# IrrigationManager.net
KiCad netlist of a schematic drawn in EAGLE
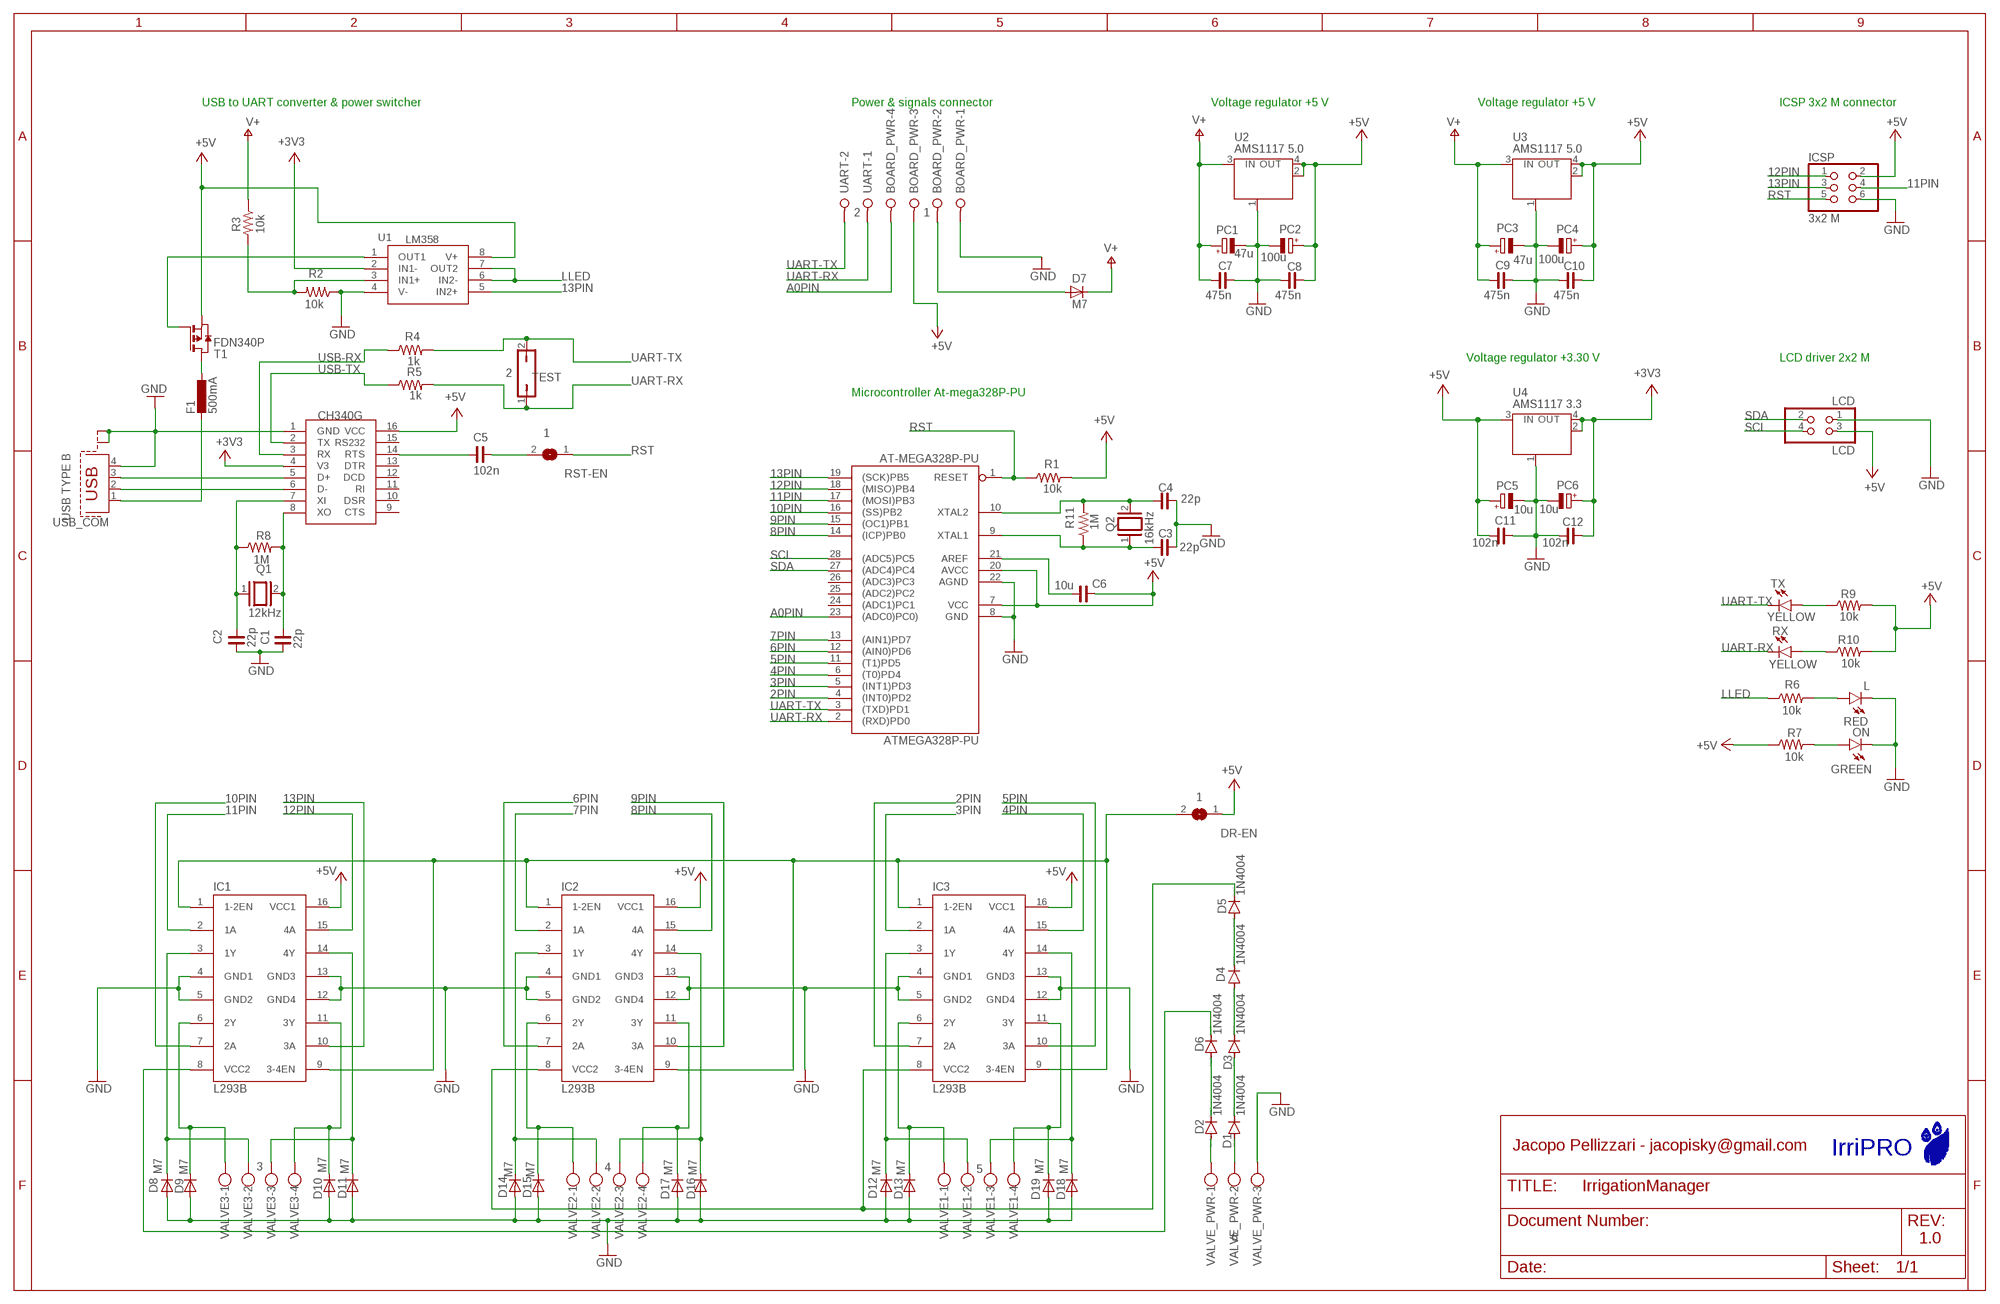
[diagram p0: schematic, sheet 1]

(export (version "E")
  (design (tool "Eeschema 10.0.6"))
  (components
    (comp (ref "AT-MEGA328P-PU")
      (value "ATMEGA328P-PU")
      (footprint "eagle-import:DIL28-3")
      (libsource (lib "eagle-import") (part "ATMEGA328P-PU"))
    )
    (comp (ref "BOARD_PWR")
      (value "1")
      (footprint "eagle-import:W237-4P")
      (libsource (lib "eagle-import") (part "con-wago-508_196_W237-04P"))
    )
    (comp (ref "C1")
      (value "22p")
      (footprint "eagle-import:C1206")
      (libsource (lib "eagle-import") (part "C_1206"))
    )
    (comp (ref "C2")
      (value "22p")
      (footprint "eagle-import:C1206")
      (libsource (lib "eagle-import") (part "C_1206"))
    )
    (comp (ref "C3")
      (value "22p")
      (footprint "eagle-import:C1206")
      (libsource (lib "eagle-import") (part "C_1206"))
    )
    (comp (ref "C4")
      (value "22p")
      (footprint "eagle-import:C1206")
      (libsource (lib "eagle-import") (part "C_1206"))
    )
    (comp (ref "C5")
      (value "102n")
      (footprint "eagle-import:C1206")
      (libsource (lib "eagle-import") (part "C_1206"))
    )
    (comp (ref "C6")
      (value "10u")
      (footprint "eagle-import:C1206")
      (libsource (lib "eagle-import") (part "C_1206"))
    )
    (comp (ref "C7")
      (value "475n")
      (footprint "eagle-import:C1206")
      (libsource (lib "eagle-import") (part "C_1206"))
    )
    (comp (ref "C8")
      (value "475n")
      (footprint "eagle-import:C1206")
      (libsource (lib "eagle-import") (part "C_1206"))
    )
    (comp (ref "C9")
      (value "475n")
      (footprint "eagle-import:C1206")
      (libsource (lib "eagle-import") (part "C_1206"))
    )
    (comp (ref "C10")
      (value "475n")
      (footprint "eagle-import:C1206")
      (libsource (lib "eagle-import") (part "C_1206"))
    )
    (comp (ref "C11")
      (value "102n")
      (footprint "eagle-import:C1206")
      (libsource (lib "eagle-import") (part "C_1206"))
    )
    (comp (ref "C12")
      (value "102n")
      (footprint "eagle-import:C1206")
      (libsource (lib "eagle-import") (part "C_1206"))
    )
    (comp (ref "D1")
      (value "1N4004")
      (footprint "eagle-import:DO41-10")
      (libsource (lib "eagle-import") (part "1N4004"))
    )
    (comp (ref "D2")
      (value "1N4004")
      (footprint "eagle-import:DO41-10")
      (libsource (lib "eagle-import") (part "1N4004"))
    )
    (comp (ref "D3")
      (value "1N4004")
      (footprint "eagle-import:DO41-10")
      (libsource (lib "eagle-import") (part "1N4004"))
    )
    (comp (ref "D4")
      (value "1N4004")
      (footprint "eagle-import:DO41-10")
      (libsource (lib "eagle-import") (part "1N4004"))
    )
    (comp (ref "D5")
      (value "1N4004")
      (footprint "eagle-import:DO41-10")
      (libsource (lib "eagle-import") (part "1N4004"))
    )
    (comp (ref "D6")
      (value "1N4004")
      (footprint "eagle-import:DO41-10")
      (libsource (lib "eagle-import") (part "1N4004"))
    )
    (comp (ref "D7")
      (value "M7")
      (footprint "eagle-import:SMB")
      (libsource (lib "eagle-import") (part "DIODE-SMB"))
    )
    (comp (ref "D8")
      (value "M7")
      (footprint "eagle-import:SMB")
      (libsource (lib "eagle-import") (part "DIODE-SMB"))
    )
    (comp (ref "D9")
      (value "M7")
      (footprint "eagle-import:SMB")
      (libsource (lib "eagle-import") (part "DIODE-SMB"))
    )
    (comp (ref "D10")
      (value "M7")
      (footprint "eagle-import:SMB")
      (libsource (lib "eagle-import") (part "DIODE-SMB"))
    )
    (comp (ref "D11")
      (value "M7")
      (footprint "eagle-import:SMB")
      (libsource (lib "eagle-import") (part "DIODE-SMB"))
    )
    (comp (ref "D12")
      (value "M7")
      (footprint "eagle-import:SMB")
      (libsource (lib "eagle-import") (part "DIODE-SMB"))
    )
    (comp (ref "D13")
      (value "M7")
      (footprint "eagle-import:SMB")
      (libsource (lib "eagle-import") (part "DIODE-SMB"))
    )
    (comp (ref "D14")
      (value "M7")
      (footprint "eagle-import:SMB")
      (libsource (lib "eagle-import") (part "DIODE-SMB"))
    )
    (comp (ref "D15")
      (value "M7")
      (footprint "eagle-import:SMB")
      (libsource (lib "eagle-import") (part "DIODE-SMB"))
    )
    (comp (ref "D16")
      (value "M7")
      (footprint "eagle-import:SMB")
      (libsource (lib "eagle-import") (part "DIODE-SMB"))
    )
    (comp (ref "D17")
      (value "M7")
      (footprint "eagle-import:SMB")
      (libsource (lib "eagle-import") (part "DIODE-SMB"))
    )
    (comp (ref "D18")
      (value "M7")
      (footprint "eagle-import:SMB")
      (libsource (lib "eagle-import") (part "DIODE-SMB"))
    )
    (comp (ref "D19")
      (value "M7")
      (footprint "eagle-import:SMB")
      (libsource (lib "eagle-import") (part "DIODE-SMB"))
    )
    (comp (ref "DR-EN")
      (value "1")
      (footprint "eagle-import:SJ")
      (libsource (lib "eagle-import") (part "SJ"))
    )
    (comp (ref "F1")
      (value "500mA")
      (footprint "eagle-import:L1812")
      (libsource (lib "eagle-import") (part "L-EUL1812"))
    )
    (comp (ref "IC1")
      (value "L293B")
      (footprint "eagle-import:DIL16")
      (fields (field (name "MPN") "L293D"))
      (libsource (lib "eagle-import") (part "L293D"))
    )
    (comp (ref "IC2")
      (value "L293B")
      (footprint "eagle-import:DIL16")
      (fields (field (name "MPN") "L293D"))
      (libsource (lib "eagle-import") (part "L293D"))
    )
    (comp (ref "IC3")
      (value "L293B")
      (footprint "eagle-import:DIL16")
      (fields (field (name "MPN") "L293D"))
      (libsource (lib "eagle-import") (part "L293D"))
    )
    (comp (ref "ICSP")
      (value "3x2 M")
      (footprint "eagle-import:2X03")
      (libsource (lib "eagle-import") (part "PINHD-2X3"))
    )
    (comp (ref "L")
      (value "RED")
      (footprint "eagle-import:CHIPLED_1206")
      (libsource (lib "eagle-import") (part "LEDCHIPLED_1206"))
    )
    (comp (ref "LCD")
      (value "LCD")
      (footprint "eagle-import:2X02")
      (libsource (lib "eagle-import") (part "PINHD-2X2"))
    )
    (comp (ref "ON")
      (value "GREEN")
      (footprint "eagle-import:CHIPLED_1206")
      (libsource (lib "eagle-import") (part "LEDCHIPLED_1206"))
    )
    (comp (ref "PC1")
      (value "47u")
      (footprint "eagle-import:PANASONIC_D")
      (libsource (lib "eagle-import") (part "CPOL-EUD"))
    )
    (comp (ref "PC2")
      (value "100u")
      (footprint "eagle-import:PANASONIC_D")
      (libsource (lib "eagle-import") (part "CPOL-EUD"))
    )
    (comp (ref "PC3")
      (value "47u")
      (footprint "eagle-import:PANASONIC_D")
      (libsource (lib "eagle-import") (part "CPOL-EUD"))
    )
    (comp (ref "PC4")
      (value "100u")
      (footprint "eagle-import:PANASONIC_D")
      (libsource (lib "eagle-import") (part "CPOL-EUD"))
    )
    (comp (ref "PC5")
      (value "10u")
      (footprint "eagle-import:153CLV-0405")
      (libsource (lib "eagle-import") (part "rcl_334_CPOL-EU153CLV-0405"))
    )
    (comp (ref "PC6")
      (value "10u")
      (footprint "eagle-import:153CLV-0405")
      (libsource (lib "eagle-import") (part "rcl_334_CPOL-EU153CLV-0405"))
    )
    (comp (ref "Q1")
      (value "12kHz")
      (footprint "eagle-import:QS")
      (libsource (lib "eagle-import") (part "XTAL/S"))
    )
    (comp (ref "Q2")
      (value "16kHz")
      (footprint "eagle-import:QS")
      (libsource (lib "eagle-import") (part "XTAL/S"))
    )
    (comp (ref "R1")
      (value "10k")
      (footprint "eagle-import:RES_1206")
      (fields
        (field (name "DIGIKEY_PART_NUMBER") "P0.0ETR-ND")
        (field (name "MANUFACTURER") "Panasonic Electronic Components")
        (field (name "MPN") "ERJ-8GEY0R00V")
        (field (name "CREATED_BY") "PCBLayout.com")
      )
      (libsource (lib "eagle-import") (part "ERJ-8GEY0R00V"))
    )
    (comp (ref "R2")
      (value "10k")
      (footprint "eagle-import:RES_1206")
      (fields
        (field (name "DIGIKEY_PART_NUMBER") "P0.0ETR-ND")
        (field (name "MANUFACTURER") "Panasonic Electronic Components")
        (field (name "MPN") "ERJ-8GEY0R00V")
        (field (name "CREATED_BY") "PCBLayout.com")
      )
      (libsource (lib "eagle-import") (part "ERJ-8GEY0R00V"))
    )
    (comp (ref "R3")
      (value "10k")
      (footprint "eagle-import:RES_1206")
      (fields
        (field (name "DIGIKEY_PART_NUMBER") "P0.0ETR-ND")
        (field (name "MANUFACTURER") "Panasonic Electronic Components")
        (field (name "MPN") "ERJ-8GEY0R00V")
        (field (name "CREATED_BY") "PCBLayout.com")
      )
      (libsource (lib "eagle-import") (part "ERJ-8GEY0R00V"))
    )
    (comp (ref "R4")
      (value "1k")
      (footprint "eagle-import:RES_1206")
      (fields
        (field (name "DIGIKEY_PART_NUMBER") "P0.0ETR-ND")
        (field (name "MANUFACTURER") "Panasonic Electronic Components")
        (field (name "MPN") "ERJ-8GEY0R00V")
        (field (name "CREATED_BY") "PCBLayout.com")
      )
      (libsource (lib "eagle-import") (part "ERJ-8GEY0R00V"))
    )
    (comp (ref "R5")
      (value "1k")
      (footprint "eagle-import:RES_1206")
      (fields
        (field (name "DIGIKEY_PART_NUMBER") "P0.0ETR-ND")
        (field (name "MANUFACTURER") "Panasonic Electronic Components")
        (field (name "MPN") "ERJ-8GEY0R00V")
        (field (name "CREATED_BY") "PCBLayout.com")
      )
      (libsource (lib "eagle-import") (part "ERJ-8GEY0R00V"))
    )
    (comp (ref "R6")
      (value "10k")
      (footprint "eagle-import:RES_1206")
      (fields
        (field (name "DIGIKEY_PART_NUMBER") "P0.0ETR-ND")
        (field (name "MANUFACTURER") "Panasonic Electronic Components")
        (field (name "MPN") "ERJ-8GEY0R00V")
        (field (name "CREATED_BY") "PCBLayout.com")
      )
      (libsource (lib "eagle-import") (part "ERJ-8GEY0R00V"))
    )
    (comp (ref "R7")
      (value "10k")
      (footprint "eagle-import:RES_1206")
      (fields
        (field (name "DIGIKEY_PART_NUMBER") "P0.0ETR-ND")
        (field (name "MANUFACTURER") "Panasonic Electronic Components")
        (field (name "MPN") "ERJ-8GEY0R00V")
        (field (name "CREATED_BY") "PCBLayout.com")
      )
      (libsource (lib "eagle-import") (part "ERJ-8GEY0R00V"))
    )
    (comp (ref "R8")
      (value "1M")
      (footprint "eagle-import:RES_1206")
      (fields
        (field (name "DIGIKEY_PART_NUMBER") "P0.0ETR-ND")
        (field (name "MANUFACTURER") "Panasonic Electronic Components")
        (field (name "MPN") "ERJ-8GEY0R00V")
        (field (name "CREATED_BY") "PCBLayout.com")
      )
      (libsource (lib "eagle-import") (part "ERJ-8GEY0R00V"))
    )
    (comp (ref "R9")
      (value "10k")
      (footprint "eagle-import:RES_1206")
      (fields
        (field (name "DIGIKEY_PART_NUMBER") "P0.0ETR-ND")
        (field (name "MANUFACTURER") "Panasonic Electronic Components")
        (field (name "MPN") "ERJ-8GEY0R00V")
        (field (name "CREATED_BY") "PCBLayout.com")
      )
      (libsource (lib "eagle-import") (part "ERJ-8GEY0R00V"))
    )
    (comp (ref "R10")
      (value "10k")
      (footprint "eagle-import:RES_1206")
      (fields
        (field (name "DIGIKEY_PART_NUMBER") "P0.0ETR-ND")
        (field (name "MANUFACTURER") "Panasonic Electronic Components")
        (field (name "MPN") "ERJ-8GEY0R00V")
        (field (name "CREATED_BY") "PCBLayout.com")
      )
      (libsource (lib "eagle-import") (part "ERJ-8GEY0R00V"))
    )
    (comp (ref "R11")
      (value "1M")
      (footprint "eagle-import:RES_1206")
      (fields
        (field (name "DIGIKEY_PART_NUMBER") "P0.0ETR-ND")
        (field (name "MANUFACTURER") "Panasonic Electronic Components")
        (field (name "MPN") "ERJ-8GEY0R00V")
        (field (name "CREATED_BY") "PCBLayout.com")
      )
      (libsource (lib "eagle-import") (part "ERJ-8GEY0R00V"))
    )
    (comp (ref "RST-EN")
      (value "1")
      (footprint "eagle-import:SJ")
      (libsource (lib "eagle-import") (part "SJ"))
    )
    (comp (ref "RX")
      (value "YELLOW")
      (footprint "eagle-import:CHIPLED_1206")
      (libsource (lib "eagle-import") (part "LEDCHIPLED_1206"))
    )
    (comp (ref "T1")
      (value "FDN340P")
      (footprint "eagle-import:SOT-23")
      (libsource (lib "eagle-import") (part "PMOSSOT23"))
    )
    (comp (ref "TEST")
      (value "2")
      (footprint "eagle-import:JP1")
      (libsource (lib "eagle-import") (part "JP1Q"))
    )
    (comp (ref "TX")
      (value "YELLOW")
      (footprint "eagle-import:CHIPLED_1206")
      (libsource (lib "eagle-import") (part "LEDCHIPLED_1206"))
    )
    (comp (ref "U$1")
      (value "CH340G")
      (footprint "eagle-import:SOIC16")
      (libsource (lib "eagle-import") (part "CH340G"))
    )
    (comp (ref "U1")
      (value "LM358")
      (footprint "eagle-import:LM358DR")
      (fields
        (field (name "DIGIKEY_PART_NUMBER") "296-1014-1-ND")
        (field (name "MANUFACTURER") "Texas Instruments")
        (field (name "MPN") "LM358DR")
        (field (name "CREATED_BY") "PCBLayout.com")
      )
      (libsource (lib "eagle-import") (part "LM358DR"))
    )
    (comp (ref "U2")
      (value "AMS1117 5.0")
      (footprint "eagle-import:SOT223")
      (libsource (lib "eagle-import") (part "MC33269ST-3.3T3"))
    )
    (comp (ref "U3")
      (value "AMS1117 5.0")
      (footprint "eagle-import:SOT223")
      (libsource (lib "eagle-import") (part "MC33269ST-3.3T3"))
    )
    (comp (ref "U4")
      (value "AMS1117 3.3")
      (footprint "eagle-import:SOT223")
      (libsource (lib "eagle-import") (part "MC33269ST-3.3T3"))
    )
    (comp (ref "UART")
      (value "2")
      (footprint "eagle-import:W237-132")
      (libsource (lib "eagle-import") (part "W237-02P"))
    )
    (comp (ref "USB_COM")
      (value "USB TYPE B")
      (footprint "eagle-import:PN61729-S")
      (libsource (lib "eagle-import") (part "PN61729-S"))
    )
    (comp (ref "VALVE1")
      (value "5")
      (footprint "eagle-import:W237-4P")
      (libsource (lib "eagle-import") (part "W237-04P"))
    )
    (comp (ref "VALVE2")
      (value "4")
      (footprint "eagle-import:W237-4P")
      (libsource (lib "eagle-import") (part "W237-04P"))
    )
    (comp (ref "VALVE3")
      (value "3")
      (footprint "eagle-import:W237-4P")
      (libsource (lib "eagle-import") (part "W237-04P"))
    )
    (comp (ref "VALVE_PWR")
      (value "6")
      (footprint "eagle-import:W237-133")
      (libsource (lib "eagle-import") (part "W237-03P"))
    )
  )
  (nets
    (net (code "1") (name "+3V3") (class "Default")
      (node (ref "C12") (pin "2") (pinfunction "2_2") (pintype "passive"))
      (node (ref "PC6") (pin "+") (pinfunction "+_+") (pintype "passive"))
      (node (ref "U$1") (pin "4") (pinfunction "V3_4") (pintype "bidirectional"))
      (node (ref "U1") (pin "2") (pinfunction "IN1-_2") (pintype "input"))
      (node (ref "U4") (pin "2") (pinfunction "OUT_2") (pintype "passive"))
      (node (ref "U4") (pin "4") (pinfunction "OUT_4") (pintype "passive"))
    )
    (net (code "2") (name "+5V") (class "Default")
      (node (ref "AT-MEGA328P-PU") (pin "20") (pinfunction "AVCC_20") (pintype "power_in"))
      (node (ref "AT-MEGA328P-PU") (pin "7") (pinfunction "VCC_7") (pintype "power_in"))
      (node (ref "BOARD_PWR") (pin "3") (pinfunction "KL_3") (pintype "passive"))
      (node (ref "C10") (pin "2") (pinfunction "2_2") (pintype "passive"))
      (node (ref "C11") (pin "1") (pinfunction "1_1") (pintype "passive"))
      (node (ref "C6") (pin "2") (pinfunction "2_2") (pintype "passive"))
      (node (ref "C8") (pin "2") (pinfunction "2_2") (pintype "passive"))
      (node (ref "DR-EN") (pin "1") (pinfunction "1_1") (pintype "passive"))
      (node (ref "IC1") (pin "16") (pinfunction "VCC1_16") (pintype "power_in"))
      (node (ref "IC2") (pin "16") (pinfunction "VCC1_16") (pintype "power_in"))
      (node (ref "IC3") (pin "16") (pinfunction "VCC1_16") (pintype "power_in"))
      (node (ref "ICSP") (pin "2") (pinfunction "2_2") (pintype "passive"))
      (node (ref "LCD") (pin "3") (pinfunction "3_3") (pintype "passive"))
      (node (ref "PC2") (pin "+") (pinfunction "+_+") (pintype "passive"))
      (node (ref "PC4") (pin "+") (pinfunction "+_+") (pintype "passive"))
      (node (ref "PC5") (pin "+") (pinfunction "+_+") (pintype "passive"))
      (node (ref "R1") (pin "2") (pinfunction "2_2") (pintype "passive"))
      (node (ref "R10") (pin "2") (pinfunction "2_2") (pintype "passive"))
      (node (ref "R7") (pin "1") (pinfunction "1_1") (pintype "passive"))
      (node (ref "R9") (pin "2") (pinfunction "2_2") (pintype "passive"))
      (node (ref "T1") (pin "2") (pinfunction "S_2") (pintype "passive"))
      (node (ref "U$1") (pin "16") (pinfunction "VCC_16") (pintype "bidirectional"))
      (node (ref "U1") (pin "8") (pinfunction "V+_8") (pintype "power_in"))
      (node (ref "U2") (pin "2") (pinfunction "OUT_2") (pintype "passive"))
      (node (ref "U2") (pin "4") (pinfunction "OUT_4") (pintype "passive"))
      (node (ref "U3") (pin "2") (pinfunction "OUT_2") (pintype "passive"))
      (node (ref "U3") (pin "4") (pinfunction "OUT_4") (pintype "passive"))
      (node (ref "U4") (pin "3") (pinfunction "IN_3") (pintype "input"))
    )
    (net (code "3") (name "/2PIN") (class "Default")
      (node (ref "AT-MEGA328P-PU") (pin "4") (pinfunction "(INT0)PD2_4") (pintype "bidirectional"))
      (node (ref "IC3") (pin "7") (pinfunction "2A_7") (pintype "input"))
    )
    (net (code "4") (name "/3PIN") (class "Default")
      (node (ref "AT-MEGA328P-PU") (pin "5") (pinfunction "(INT1)PD3_5") (pintype "bidirectional"))
      (node (ref "IC3") (pin "2") (pinfunction "1A_2") (pintype "input"))
    )
    (net (code "5") (name "/4PIN") (class "Default")
      (node (ref "AT-MEGA328P-PU") (pin "6") (pinfunction "(T0)PD4_6") (pintype "bidirectional"))
      (node (ref "IC3") (pin "15") (pinfunction "4A_15") (pintype "input"))
    )
    (net (code "6") (name "/5PIN") (class "Default")
      (node (ref "AT-MEGA328P-PU") (pin "11") (pinfunction "(T1)PD5_11") (pintype "bidirectional"))
      (node (ref "IC3") (pin "10") (pinfunction "3A_10") (pintype "input"))
    )
    (net (code "7") (name "/6PIN") (class "Default")
      (node (ref "AT-MEGA328P-PU") (pin "12") (pinfunction "(AIN0)PD6_12") (pintype "bidirectional"))
      (node (ref "IC2") (pin "7") (pinfunction "2A_7") (pintype "input"))
    )
    (net (code "8") (name "/7PIN") (class "Default")
      (node (ref "AT-MEGA328P-PU") (pin "13") (pinfunction "(AIN1)PD7_13") (pintype "bidirectional"))
      (node (ref "IC2") (pin "2") (pinfunction "1A_2") (pintype "input"))
    )
    (net (code "9") (name "/8PIN") (class "Default")
      (node (ref "AT-MEGA328P-PU") (pin "14") (pinfunction "(ICP)PB0_14") (pintype "bidirectional"))
      (node (ref "IC2") (pin "15") (pinfunction "4A_15") (pintype "input"))
    )
    (net (code "10") (name "/9PIN") (class "Default")
      (node (ref "AT-MEGA328P-PU") (pin "15") (pinfunction "(OC1)PB1_15") (pintype "bidirectional"))
      (node (ref "IC2") (pin "10") (pinfunction "3A_10") (pintype "input"))
    )
    (net (code "11") (name "/10PIN") (class "Default")
      (node (ref "AT-MEGA328P-PU") (pin "16") (pinfunction "(SS)PB2_16") (pintype "bidirectional"))
      (node (ref "IC1") (pin "7") (pinfunction "2A_7") (pintype "input"))
    )
    (net (code "12") (name "/11PIN") (class "Default")
      (node (ref "AT-MEGA328P-PU") (pin "17") (pinfunction "(MOSI)PB3_17") (pintype "bidirectional"))
      (node (ref "IC1") (pin "2") (pinfunction "1A_2") (pintype "input"))
      (node (ref "ICSP") (pin "4") (pinfunction "4_4") (pintype "passive"))
    )
    (net (code "13") (name "/12PIN") (class "Default")
      (node (ref "AT-MEGA328P-PU") (pin "18") (pinfunction "(MISO)PB4_18") (pintype "bidirectional"))
      (node (ref "IC1") (pin "15") (pinfunction "4A_15") (pintype "input"))
      (node (ref "ICSP") (pin "1") (pinfunction "1_1") (pintype "passive"))
    )
    (net (code "14") (name "/13PIN") (class "Default")
      (node (ref "AT-MEGA328P-PU") (pin "19") (pinfunction "(SCK)PB5_19") (pintype "bidirectional"))
      (node (ref "IC1") (pin "10") (pinfunction "3A_10") (pintype "input"))
      (node (ref "ICSP") (pin "3") (pinfunction "3_3") (pintype "passive"))
      (node (ref "U1") (pin "5") (pinfunction "IN2+_5") (pintype "input"))
    )
    (net (code "15") (name "/A0PIN") (class "Default")
      (node (ref "AT-MEGA328P-PU") (pin "23") (pinfunction "(ADC0)PC0)_23") (pintype "bidirectional"))
      (node (ref "BOARD_PWR") (pin "4") (pinfunction "KL_4") (pintype "passive"))
    )
    (net (code "16") (name "/LLED") (class "Default")
      (node (ref "R6") (pin "1") (pinfunction "1_1") (pintype "passive"))
      (node (ref "U1") (pin "6") (pinfunction "IN2-_6") (pintype "input"))
      (node (ref "U1") (pin "7") (pinfunction "OUT2_7") (pintype "output"))
    )
    (net (code "17") (name "/RST") (class "Default")
      (node (ref "AT-MEGA328P-PU") (pin "1") (pinfunction "RESET_1") (pintype "input"))
      (node (ref "ICSP") (pin "5") (pinfunction "5_5") (pintype "passive"))
      (node (ref "R1") (pin "1") (pinfunction "1_1") (pintype "passive"))
      (node (ref "RST-EN") (pin "1") (pinfunction "1_1") (pintype "passive"))
    )
    (net (code "18") (name "/SCL") (class "Default")
      (node (ref "AT-MEGA328P-PU") (pin "28") (pinfunction "(ADC5)PC5_28") (pintype "bidirectional"))
      (node (ref "LCD") (pin "4") (pinfunction "4_4") (pintype "passive"))
    )
    (net (code "19") (name "/SDA") (class "Default")
      (node (ref "AT-MEGA328P-PU") (pin "27") (pinfunction "(ADC4)PC4_27") (pintype "bidirectional"))
      (node (ref "LCD") (pin "2") (pinfunction "2_2") (pintype "passive"))
    )
    (net (code "20") (name "/UART-RX") (class "Default")
      (node (ref "AT-MEGA328P-PU") (pin "2") (pinfunction "(RXD)PD0_2") (pintype "bidirectional"))
      (node (ref "R5") (pin "2") (pinfunction "2_2") (pintype "passive"))
      (node (ref "RX") (pin "C") (pinfunction "C_C") (pintype "passive"))
      (node (ref "TEST") (pin "1") (pinfunction "1_1") (pintype "passive"))
      (node (ref "UART") (pin "1") (pinfunction "KL_1") (pintype "passive"))
    )
    (net (code "21") (name "/UART-TX") (class "Default")
      (node (ref "AT-MEGA328P-PU") (pin "3") (pinfunction "(TXD)PD1_3") (pintype "bidirectional"))
      (node (ref "R4") (pin "2") (pinfunction "2_2") (pintype "passive"))
      (node (ref "TEST") (pin "2") (pinfunction "2_2") (pintype "passive"))
      (node (ref "TX") (pin "C") (pinfunction "C_C") (pintype "passive"))
      (node (ref "UART") (pin "2") (pinfunction "KL_2") (pintype "passive"))
    )
    (net (code "22") (name "/USB-RX") (class "Default")
      (node (ref "R4") (pin "1") (pinfunction "1_1") (pintype "passive"))
      (node (ref "U$1") (pin "3") (pinfunction "RX_3") (pintype "bidirectional"))
    )
    (net (code "23") (name "/USB-TX") (class "Default")
      (node (ref "R5") (pin "1") (pinfunction "1_1") (pintype "passive"))
      (node (ref "U$1") (pin "2") (pinfunction "TX_2") (pintype "bidirectional"))
    )
    (net (code "24") (name "GND") (class "Default")
      (node (ref "AT-MEGA328P-PU") (pin "22") (pinfunction "AGND_22") (pintype "power_in"))
      (node (ref "AT-MEGA328P-PU") (pin "8") (pinfunction "GND_8") (pintype "power_in"))
      (node (ref "BOARD_PWR") (pin "1") (pinfunction "KL_1") (pintype "passive"))
      (node (ref "C1") (pin "1") (pinfunction "1_1") (pintype "passive"))
      (node (ref "C10") (pin "1") (pinfunction "1_1") (pintype "passive"))
      (node (ref "C11") (pin "2") (pinfunction "2_2") (pintype "passive"))
      (node (ref "C12") (pin "1") (pinfunction "1_1") (pintype "passive"))
      (node (ref "C2") (pin "1") (pinfunction "1_1") (pintype "passive"))
      (node (ref "C3") (pin "2") (pinfunction "2_2") (pintype "passive"))
      (node (ref "C4") (pin "2") (pinfunction "2_2") (pintype "passive"))
      (node (ref "C7") (pin "2") (pinfunction "2_2") (pintype "passive"))
      (node (ref "C8") (pin "1") (pinfunction "1_1") (pintype "passive"))
      (node (ref "C9") (pin "2") (pinfunction "2_2") (pintype "passive"))
      (node (ref "D10") (pin "A") (pinfunction "A_A") (pintype "passive"))
      (node (ref "D11") (pin "A") (pinfunction "A_A") (pintype "passive"))
      (node (ref "D12") (pin "A") (pinfunction "A_A") (pintype "passive"))
      (node (ref "D13") (pin "A") (pinfunction "A_A") (pintype "passive"))
      (node (ref "D14") (pin "A") (pinfunction "A_A") (pintype "passive"))
      (node (ref "D15") (pin "A") (pinfunction "A_A") (pintype "passive"))
      (node (ref "D16") (pin "A") (pinfunction "A_A") (pintype "passive"))
      (node (ref "D17") (pin "A") (pinfunction "A_A") (pintype "passive"))
      (node (ref "D18") (pin "A") (pinfunction "A_A") (pintype "passive"))
      (node (ref "D19") (pin "A") (pinfunction "A_A") (pintype "passive"))
      (node (ref "D8") (pin "A") (pinfunction "A_A") (pintype "passive"))
      (node (ref "D9") (pin "A") (pinfunction "A_A") (pintype "passive"))
      (node (ref "IC1") (pin "12") (pinfunction "GND4_12") (pintype "power_in"))
      (node (ref "IC1") (pin "13") (pinfunction "GND3_13") (pintype "power_in"))
      (node (ref "IC1") (pin "4") (pinfunction "GND1_4") (pintype "power_in"))
      (node (ref "IC1") (pin "5") (pinfunction "GND2_5") (pintype "power_in"))
      (node (ref "IC2") (pin "12") (pinfunction "GND4_12") (pintype "power_in"))
      (node (ref "IC2") (pin "13") (pinfunction "GND3_13") (pintype "power_in"))
      (node (ref "IC2") (pin "4") (pinfunction "GND1_4") (pintype "power_in"))
      (node (ref "IC2") (pin "5") (pinfunction "GND2_5") (pintype "power_in"))
      (node (ref "IC3") (pin "12") (pinfunction "GND4_12") (pintype "power_in"))
      (node (ref "IC3") (pin "13") (pinfunction "GND3_13") (pintype "power_in"))
      (node (ref "IC3") (pin "4") (pinfunction "GND1_4") (pintype "power_in"))
      (node (ref "IC3") (pin "5") (pinfunction "GND2_5") (pintype "power_in"))
      (node (ref "ICSP") (pin "6") (pinfunction "6_6") (pintype "passive"))
      (node (ref "L") (pin "C") (pinfunction "C_C") (pintype "passive"))
      (node (ref "LCD") (pin "1") (pinfunction "1_1") (pintype "passive"))
      (node (ref "ON") (pin "C") (pinfunction "C_C") (pintype "passive"))
      (node (ref "PC1") (pin "-") (pinfunction "-_-") (pintype "passive"))
      (node (ref "PC2") (pin "-") (pinfunction "-_-") (pintype "passive"))
      (node (ref "PC3") (pin "-") (pinfunction "-_-") (pintype "passive"))
      (node (ref "PC4") (pin "-") (pinfunction "-_-") (pintype "passive"))
      (node (ref "PC5") (pin "-") (pinfunction "-_-") (pintype "passive"))
      (node (ref "PC6") (pin "-") (pinfunction "-_-") (pintype "passive"))
      (node (ref "R2") (pin "1") (pinfunction "1_1") (pintype "passive"))
      (node (ref "U$1") (pin "1") (pinfunction "GND_1") (pintype "bidirectional"))
      (node (ref "U1") (pin "4") (pinfunction "V-_4") (pintype "power_in"))
      (node (ref "U2") (pin "1") (pinfunction "GND/ADJ_1") (pintype "input"))
      (node (ref "U3") (pin "1") (pinfunction "GND/ADJ_1") (pintype "input"))
      (node (ref "U4") (pin "1") (pinfunction "GND/ADJ_1") (pintype "input"))
      (node (ref "USB_COM") (pin "4") (pinfunction "4_4") (pintype "passive"))
      (node (ref "USB_COM") (pin "S1") (pinfunction "S1_S1") (pintype "passive"))
      (node (ref "USB_COM") (pin "S2") (pinfunction "S2_S2") (pintype "passive"))
      (node (ref "VALVE_PWR") (pin "3") (pinfunction "KL_3") (pintype "passive"))
    )
    (net (code "25") (name "Net-(AT-MEGA328P-PU-AREF)") (class "Default")
      (node (ref "AT-MEGA328P-PU") (pin "21") (pinfunction "AREF_21") (pintype "passive"))
      (node (ref "C6") (pin "1") (pinfunction "1_1") (pintype "passive"))
    )
    (net (code "26") (name "Net-(AT-MEGA328P-PU-XTAL1)") (class "Default")
      (node (ref "AT-MEGA328P-PU") (pin "9") (pinfunction "XTAL1_9") (pintype "bidirectional"))
      (node (ref "C3") (pin "1") (pinfunction "1_1") (pintype "passive"))
      (node (ref "Q2") (pin "1") (pinfunction "1_1") (pintype "passive"))
      (node (ref "R11") (pin "1") (pinfunction "1_1") (pintype "passive"))
    )
    (net (code "27") (name "Net-(AT-MEGA328P-PU-XTAL2)") (class "Default")
      (node (ref "AT-MEGA328P-PU") (pin "10") (pinfunction "XTAL2_10") (pintype "bidirectional"))
      (node (ref "C4") (pin "1") (pinfunction "1_1") (pintype "passive"))
      (node (ref "Q2") (pin "2") (pinfunction "2_2") (pintype "passive"))
      (node (ref "R11") (pin "2") (pinfunction "2_2") (pintype "passive"))
    )
    (net (code "28") (name "Net-(BOARD_PWRB-KL)") (class "Default")
      (node (ref "BOARD_PWR") (pin "2") (pinfunction "KL_2") (pintype "passive"))
      (node (ref "D7") (pin "A") (pinfunction "A_A") (pintype "passive"))
    )
    (net (code "29") (name "Net-(C5-Pad2)") (class "Default")
      (node (ref "C5") (pin "2") (pinfunction "2_2") (pintype "passive"))
      (node (ref "RST-EN") (pin "2") (pinfunction "2_2") (pintype "passive"))
    )
    (net (code "30") (name "Net-(D1-PadC)") (class "Default")
      (node (ref "D1") (pin "C") (pinfunction "C_C") (pintype "passive"))
      (node (ref "D3") (pin "A") (pinfunction "A_A") (pintype "passive"))
    )
    (net (code "31") (name "Net-(D2-PadC)") (class "Default")
      (node (ref "D2") (pin "C") (pinfunction "C_C") (pintype "passive"))
      (node (ref "D6") (pin "A") (pinfunction "A_A") (pintype "passive"))
    )
    (net (code "32") (name "Net-(D3-PadC)") (class "Default")
      (node (ref "D3") (pin "C") (pinfunction "C_C") (pintype "passive"))
      (node (ref "D4") (pin "A") (pinfunction "A_A") (pintype "passive"))
    )
    (net (code "33") (name "Net-(D4-PadC)") (class "Default")
      (node (ref "D4") (pin "C") (pinfunction "C_C") (pintype "passive"))
      (node (ref "D5") (pin "A") (pinfunction "A_A") (pintype "passive"))
    )
    (net (code "34") (name "Net-(F1-Pad2)") (class "Default")
      (node (ref "F1") (pin "2") (pinfunction "2_2") (pintype "passive"))
      (node (ref "USB_COM") (pin "1") (pinfunction "1_1") (pintype "passive"))
    )
    (net (code "35") (name "Net-(IC1-1-2EN)") (class "Default")
      (node (ref "DR-EN") (pin "2") (pinfunction "2_2") (pintype "passive"))
      (node (ref "IC1") (pin "1") (pinfunction "1-2EN_1") (pintype "input"))
      (node (ref "IC1") (pin "9") (pinfunction "3-4EN_9") (pintype "input"))
      (node (ref "IC2") (pin "1") (pinfunction "1-2EN_1") (pintype "input"))
      (node (ref "IC2") (pin "9") (pinfunction "3-4EN_9") (pintype "input"))
      (node (ref "IC3") (pin "1") (pinfunction "1-2EN_1") (pintype "input"))
      (node (ref "IC3") (pin "9") (pinfunction "3-4EN_9") (pintype "input"))
    )
    (net (code "36") (name "Net-(IC1-1Y)") (class "Default")
      (node (ref "D8") (pin "C") (pinfunction "C_C") (pintype "passive"))
      (node (ref "IC1") (pin "3") (pinfunction "1Y_3") (pintype "output"))
      (node (ref "VALVE3") (pin "2") (pinfunction "KL_2") (pintype "passive"))
    )
    (net (code "37") (name "Net-(IC1-2Y)") (class "Default")
      (node (ref "D9") (pin "C") (pinfunction "C_C") (pintype "passive"))
      (node (ref "IC1") (pin "6") (pinfunction "2Y_6") (pintype "output"))
      (node (ref "VALVE3") (pin "1") (pinfunction "KL_1") (pintype "passive"))
    )
    (net (code "38") (name "Net-(IC1-3Y)") (class "Default")
      (node (ref "D10") (pin "C") (pinfunction "C_C") (pintype "passive"))
      (node (ref "IC1") (pin "11") (pinfunction "3Y_11") (pintype "output"))
      (node (ref "VALVE3") (pin "4") (pinfunction "KL_4") (pintype "passive"))
    )
    (net (code "39") (name "Net-(IC1-4Y)") (class "Default")
      (node (ref "D11") (pin "C") (pinfunction "C_C") (pintype "passive"))
      (node (ref "IC1") (pin "14") (pinfunction "4Y_14") (pintype "output"))
      (node (ref "VALVE3") (pin "3") (pinfunction "KL_3") (pintype "passive"))
    )
    (net (code "40") (name "Net-(IC1-VCC2)") (class "Default")
      (node (ref "D6") (pin "C") (pinfunction "C_C") (pintype "passive"))
      (node (ref "IC1") (pin "8") (pinfunction "VCC2_8") (pintype "power_in"))
    )
    (net (code "41") (name "Net-(IC2-1Y)") (class "Default")
      (node (ref "D14") (pin "C") (pinfunction "C_C") (pintype "passive"))
      (node (ref "IC2") (pin "3") (pinfunction "1Y_3") (pintype "output"))
      (node (ref "VALVE2") (pin "2") (pinfunction "KL_2") (pintype "passive"))
    )
    (net (code "42") (name "Net-(IC2-2Y)") (class "Default")
      (node (ref "D15") (pin "C") (pinfunction "C_C") (pintype "passive"))
      (node (ref "IC2") (pin "6") (pinfunction "2Y_6") (pintype "output"))
      (node (ref "VALVE2") (pin "1") (pinfunction "KL_1") (pintype "passive"))
    )
    (net (code "43") (name "Net-(IC2-3Y)") (class "Default")
      (node (ref "D17") (pin "C") (pinfunction "C_C") (pintype "passive"))
      (node (ref "IC2") (pin "11") (pinfunction "3Y_11") (pintype "output"))
      (node (ref "VALVE2") (pin "4") (pinfunction "KL_4") (pintype "passive"))
    )
    (net (code "44") (name "Net-(IC2-4Y)") (class "Default")
      (node (ref "D16") (pin "C") (pinfunction "C_C") (pintype "passive"))
      (node (ref "IC2") (pin "14") (pinfunction "4Y_14") (pintype "output"))
      (node (ref "VALVE2") (pin "3") (pinfunction "KL_3") (pintype "passive"))
    )
    (net (code "45") (name "Net-(IC2-VCC2)") (class "Default")
      (node (ref "D5") (pin "C") (pinfunction "C_C") (pintype "passive"))
      (node (ref "IC2") (pin "8") (pinfunction "VCC2_8") (pintype "power_in"))
      (node (ref "IC3") (pin "8") (pinfunction "VCC2_8") (pintype "power_in"))
    )
    (net (code "46") (name "Net-(IC3-1Y)") (class "Default")
      (node (ref "D12") (pin "C") (pinfunction "C_C") (pintype "passive"))
      (node (ref "IC3") (pin "3") (pinfunction "1Y_3") (pintype "output"))
      (node (ref "VALVE1") (pin "2") (pinfunction "KL_2") (pintype "passive"))
    )
    (net (code "47") (name "Net-(IC3-2Y)") (class "Default")
      (node (ref "D13") (pin "C") (pinfunction "C_C") (pintype "passive"))
      (node (ref "IC3") (pin "6") (pinfunction "2Y_6") (pintype "output"))
      (node (ref "VALVE1") (pin "1") (pinfunction "KL_1") (pintype "passive"))
    )
    (net (code "48") (name "Net-(IC3-3Y)") (class "Default")
      (node (ref "D19") (pin "C") (pinfunction "C_C") (pintype "passive"))
      (node (ref "IC3") (pin "11") (pinfunction "3Y_11") (pintype "output"))
      (node (ref "VALVE1") (pin "4") (pinfunction "KL_4") (pintype "passive"))
    )
    (net (code "49") (name "Net-(IC3-4Y)") (class "Default")
      (node (ref "D18") (pin "C") (pinfunction "C_C") (pintype "passive"))
      (node (ref "IC3") (pin "14") (pinfunction "4Y_14") (pintype "output"))
      (node (ref "VALVE1") (pin "3") (pinfunction "KL_3") (pintype "passive"))
    )
    (net (code "50") (name "Net-(L-PadA)") (class "Default")
      (node (ref "L") (pin "A") (pinfunction "A_A") (pintype "passive"))
      (node (ref "R6") (pin "2") (pinfunction "2_2") (pintype "passive"))
    )
    (net (code "51") (name "Net-(ON-PadA)") (class "Default")
      (node (ref "ON") (pin "A") (pinfunction "A_A") (pintype "passive"))
      (node (ref "R7") (pin "2") (pinfunction "2_2") (pintype "passive"))
    )
    (net (code "52") (name "Net-(R9-Pad1)") (class "Default")
      (node (ref "R9") (pin "1") (pinfunction "1_1") (pintype "passive"))
      (node (ref "TX") (pin "A") (pinfunction "A_A") (pintype "passive"))
    )
    (net (code "53") (name "Net-(R10-Pad1)") (class "Default")
      (node (ref "R10") (pin "1") (pinfunction "1_1") (pintype "passive"))
      (node (ref "RX") (pin "A") (pinfunction "A_A") (pintype "passive"))
    )
    (net (code "54") (name "Net-(T1-D)") (class "Default")
      (node (ref "F1") (pin "1") (pinfunction "1_1") (pintype "passive"))
      (node (ref "T1") (pin "1") (pinfunction "D_1") (pintype "passive"))
    )
    (net (code "55") (name "Net-(T1-G)") (class "Default")
      (node (ref "T1") (pin "3") (pinfunction "G_3") (pintype "passive"))
      (node (ref "U1") (pin "1") (pinfunction "OUT1_1") (pintype "output"))
    )
    (net (code "56") (name "Net-(U$1-D+)") (class "Default")
      (node (ref "U$1") (pin "5") (pinfunction "D+_5") (pintype "bidirectional"))
      (node (ref "USB_COM") (pin "3") (pinfunction "3_3") (pintype "passive"))
    )
    (net (code "57") (name "Net-(U$1-D-)") (class "Default")
      (node (ref "U$1") (pin "6") (pinfunction "D-_6") (pintype "bidirectional"))
      (node (ref "USB_COM") (pin "2") (pinfunction "2_2") (pintype "passive"))
    )
    (net (code "58") (name "Net-(U$1-RTS)") (class "Default")
      (node (ref "C5") (pin "1") (pinfunction "1_1") (pintype "passive"))
      (node (ref "U$1") (pin "14") (pinfunction "RTS_14") (pintype "bidirectional"))
    )
    (net (code "59") (name "Net-(U$1-XI)") (class "Default")
      (node (ref "C2") (pin "2") (pinfunction "2_2") (pintype "passive"))
      (node (ref "Q1") (pin "1") (pinfunction "1_1") (pintype "passive"))
      (node (ref "R8") (pin "1") (pinfunction "1_1") (pintype "passive"))
      (node (ref "U$1") (pin "7") (pinfunction "XI_7") (pintype "bidirectional"))
    )
    (net (code "60") (name "Net-(U$1-XO)") (class "Default")
      (node (ref "C1") (pin "2") (pinfunction "2_2") (pintype "passive"))
      (node (ref "Q1") (pin "2") (pinfunction "2_2") (pintype "passive"))
      (node (ref "R8") (pin "2") (pinfunction "2_2") (pintype "passive"))
      (node (ref "U$1") (pin "8") (pinfunction "XO_8") (pintype "bidirectional"))
    )
    (net (code "61") (name "Net-(U1-IN1+)") (class "Default")
      (node (ref "R2") (pin "2") (pinfunction "2_2") (pintype "passive"))
      (node (ref "R3") (pin "2") (pinfunction "2_2") (pintype "passive"))
      (node (ref "U1") (pin "3") (pinfunction "IN1+_3") (pintype "input"))
    )
    (net (code "62") (name "Net-(VALVE_PWRA-KL)") (class "Default")
      (node (ref "D2") (pin "A") (pinfunction "A_A") (pintype "passive"))
      (node (ref "VALVE_PWR") (pin "1") (pinfunction "KL_1") (pintype "passive"))
    )
    (net (code "63") (name "Net-(VALVE_PWRB-KL)") (class "Default")
      (node (ref "D1") (pin "A") (pinfunction "A_A") (pintype "passive"))
      (node (ref "VALVE_PWR") (pin "2") (pinfunction "KL_2") (pintype "passive"))
    )
    (net (code "64") (name "V+") (class "Default")
      (node (ref "C7") (pin "1") (pinfunction "1_1") (pintype "passive"))
      (node (ref "C9") (pin "1") (pinfunction "1_1") (pintype "passive"))
      (node (ref "D7") (pin "C") (pinfunction "C_C") (pintype "passive"))
      (node (ref "PC1") (pin "+") (pinfunction "+_+") (pintype "passive"))
      (node (ref "PC3") (pin "+") (pinfunction "+_+") (pintype "passive"))
      (node (ref "R3") (pin "1") (pinfunction "1_1") (pintype "passive"))
      (node (ref "U2") (pin "3") (pinfunction "IN_3") (pintype "input"))
      (node (ref "U3") (pin "3") (pinfunction "IN_3") (pintype "input"))
    )
    (net (code "65") (name "unconnected-(AT-MEGA328P-PU-(ADC1)PC1-Pad24)") (class "Default")
      (node (ref "AT-MEGA328P-PU") (pin "24") (pinfunction "(ADC1)PC1_24") (pintype "bidirectional"))
    )
    (net (code "66") (name "unconnected-(AT-MEGA328P-PU-(ADC2)PC2-Pad25)") (class "Default")
      (node (ref "AT-MEGA328P-PU") (pin "25") (pinfunction "(ADC2)PC2_25") (pintype "bidirectional"))
    )
    (net (code "67") (name "unconnected-(AT-MEGA328P-PU-(ADC3)PC3-Pad26)") (class "Default")
      (node (ref "AT-MEGA328P-PU") (pin "26") (pinfunction "(ADC3)PC3_26") (pintype "bidirectional"))
    )
    (net (code "68") (name "unconnected-(U$1-CTS-Pad9)") (class "Default")
      (node (ref "U$1") (pin "9") (pinfunction "CTS_9") (pintype "bidirectional"))
    )
    (net (code "69") (name "unconnected-(U$1-DCD-Pad12)") (class "Default")
      (node (ref "U$1") (pin "12") (pinfunction "DCD_12") (pintype "bidirectional"))
    )
    (net (code "70") (name "unconnected-(U$1-DSR-Pad10)") (class "Default")
      (node (ref "U$1") (pin "10") (pinfunction "DSR_10") (pintype "bidirectional"))
    )
    (net (code "71") (name "unconnected-(U$1-DTR-Pad13)") (class "Default")
      (node (ref "U$1") (pin "13") (pinfunction "DTR_13") (pintype "bidirectional"))
    )
    (net (code "72") (name "unconnected-(U$1-RI-Pad11)") (class "Default")
      (node (ref "U$1") (pin "11") (pinfunction "RI_11") (pintype "bidirectional"))
    )
    (net (code "73") (name "unconnected-(U$1-RS232-Pad15)") (class "Default")
      (node (ref "U$1") (pin "15") (pinfunction "RS232_15") (pintype "bidirectional"))
    )
  )
)
